# SNAC_hdmi-mini.net
KiCad netlist of a schematic drawn in EAGLE
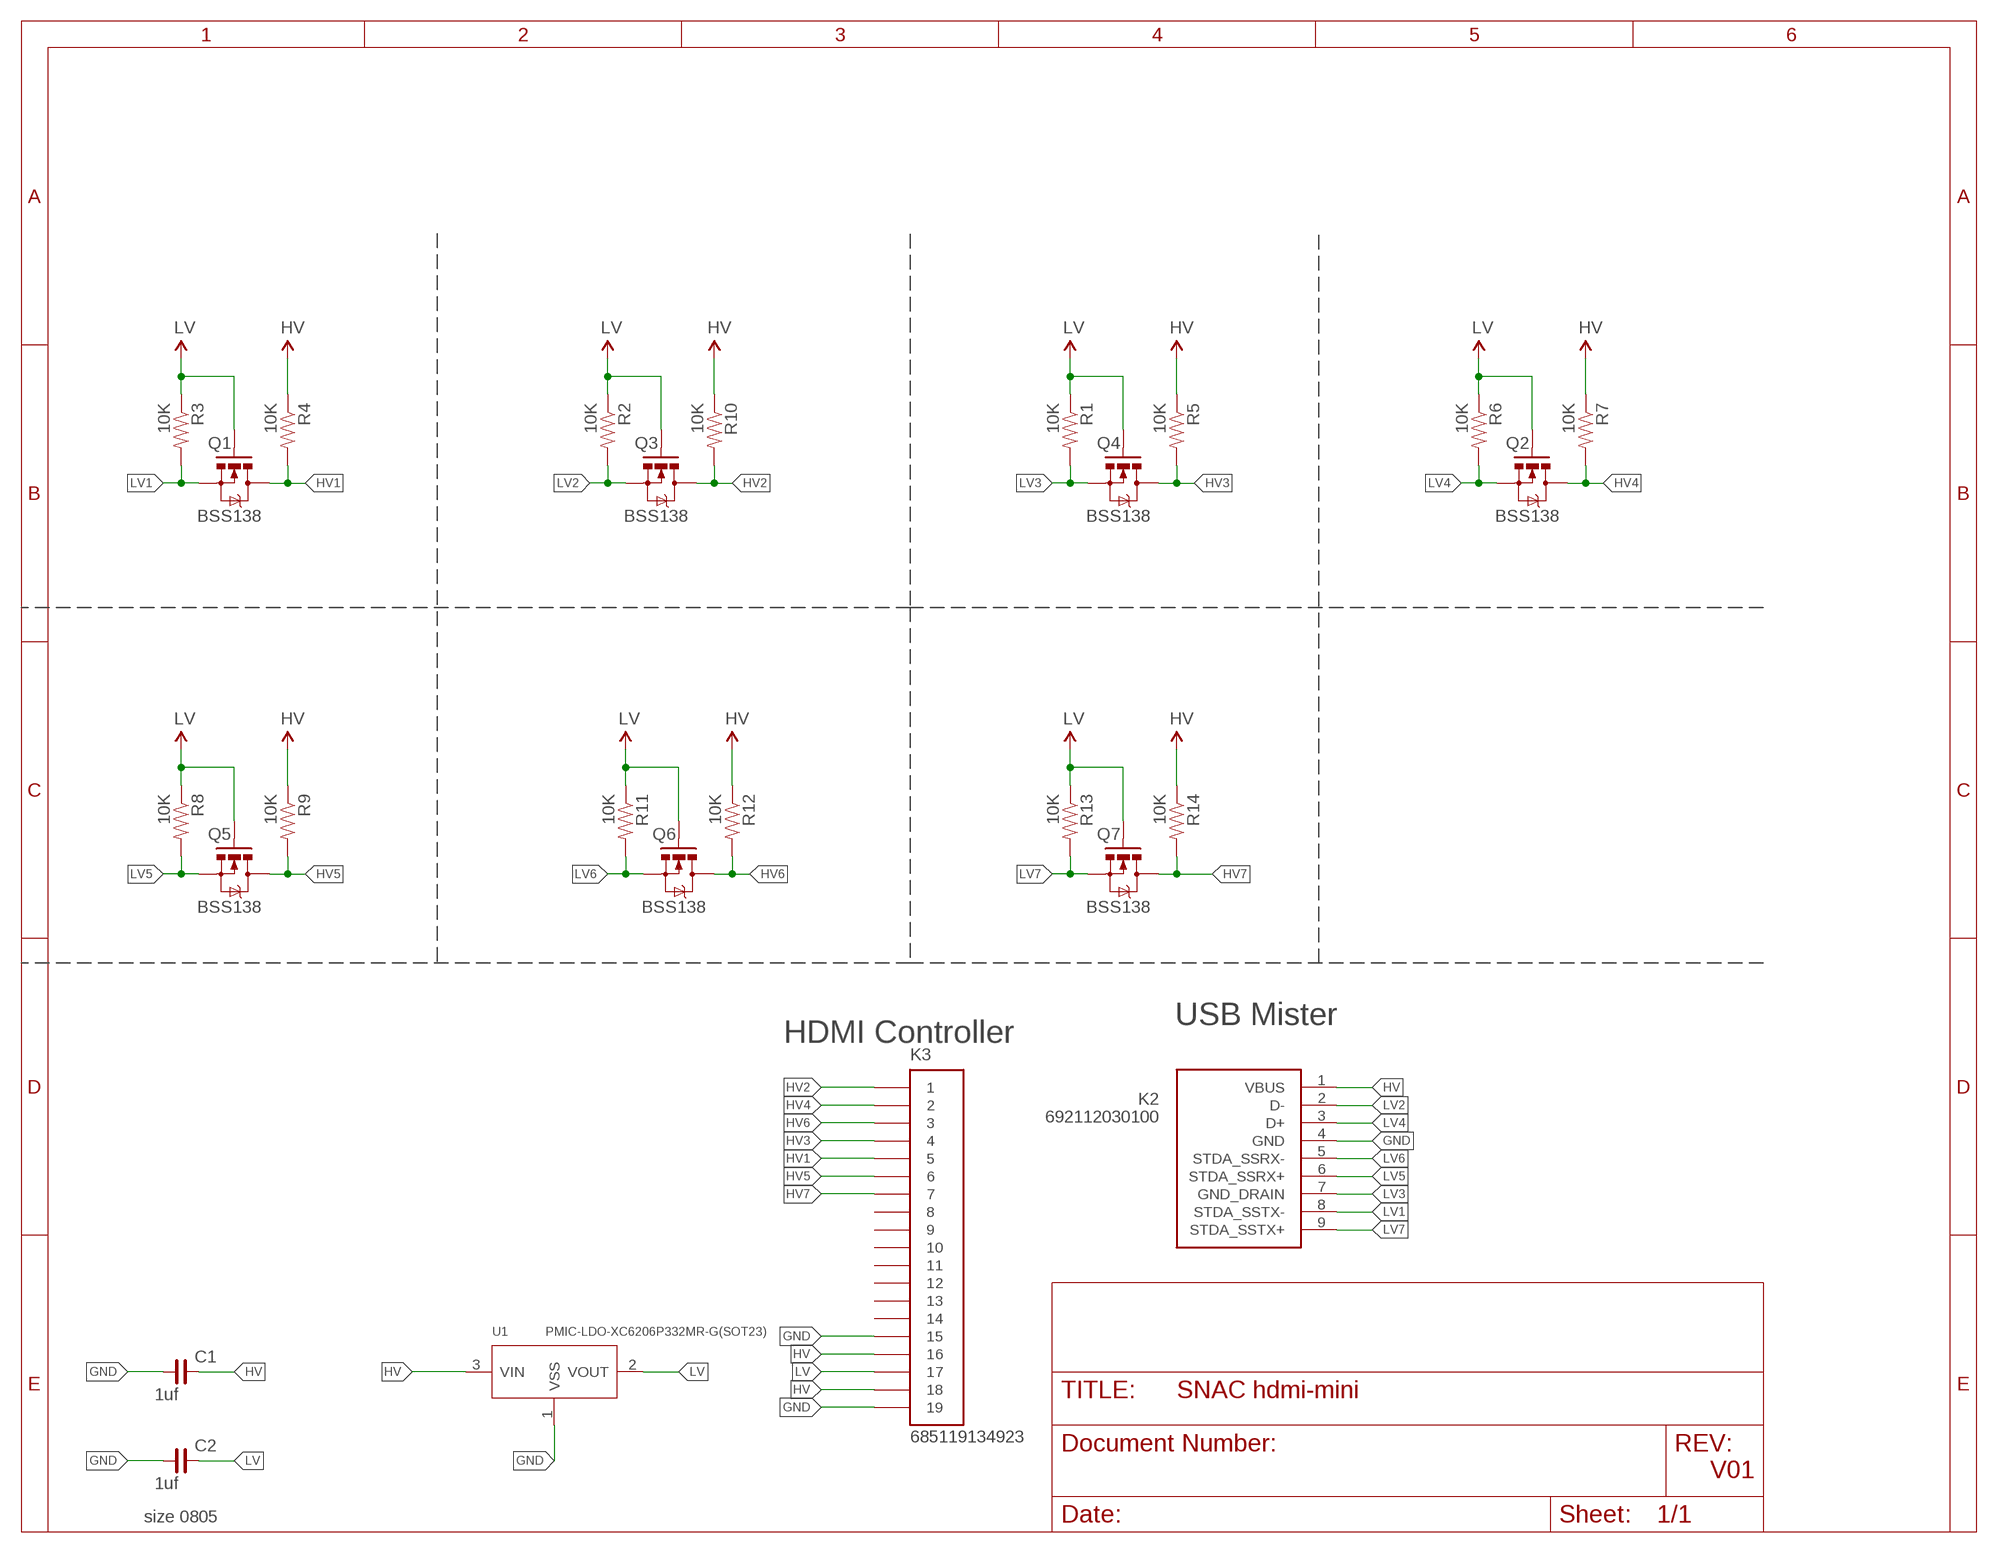
[diagram p0: schematic, sheet 1]

(export (version "E")
  (design (tool "Eeschema 10.0.6"))
  (components
    (comp (ref "C1")
      (value "1uf")
      (footprint "eagle-import:C0805")
      (libsource (lib "eagle-import") (part "C_0805"))
    )
    (comp (ref "C2")
      (value "1uf")
      (footprint "eagle-import:C0805")
      (libsource (lib "eagle-import") (part "C_0805"))
    )
    (comp (ref "K2")
      (value "692112030100")
      (footprint "eagle-import:692112030100")
      (libsource (lib "eagle-import") (part "692112030100"))
    )
    (comp (ref "K3")
      (value "685119134923")
      (footprint "eagle-import:685119134923")
      (libsource (lib "eagle-import") (part "685119134923"))
    )
    (comp (ref "Q1")
      (value "BSS138")
      (footprint "eagle-import:SOT23-3")
      (libsource (lib "eagle-import") (part "MOSFET-NCHANNELSMD"))
    )
    (comp (ref "Q2")
      (value "BSS138")
      (footprint "eagle-import:SOT23-3")
      (libsource (lib "eagle-import") (part "MOSFET-NCHANNELSMD"))
    )
    (comp (ref "Q3")
      (value "BSS138")
      (footprint "eagle-import:SOT23-3")
      (libsource (lib "eagle-import") (part "MOSFET-NCHANNELSMD"))
    )
    (comp (ref "Q4")
      (value "BSS138")
      (footprint "eagle-import:SOT23-3")
      (libsource (lib "eagle-import") (part "MOSFET-NCHANNELSMD"))
    )
    (comp (ref "Q5")
      (value "BSS138")
      (footprint "eagle-import:SOT23-3")
      (libsource (lib "eagle-import") (part "MOSFET-NCHANNELSMD"))
    )
    (comp (ref "Q6")
      (value "BSS138")
      (footprint "eagle-import:SOT23-3")
      (libsource (lib "eagle-import") (part "MOSFET-NCHANNELSMD"))
    )
    (comp (ref "Q7")
      (value "BSS138")
      (footprint "eagle-import:SOT23-3")
      (libsource (lib "eagle-import") (part "MOSFET-NCHANNELSMD"))
    )
    (comp (ref "R1")
      (value "10K")
      (footprint "eagle-import:0603-RES")
      (libsource (lib "eagle-import") (part "RESISTOR0603-RES"))
    )
    (comp (ref "R2")
      (value "10K")
      (footprint "eagle-import:0603-RES")
      (libsource (lib "eagle-import") (part "RESISTOR0603-RES"))
    )
    (comp (ref "R3")
      (value "10K")
      (footprint "eagle-import:0603-RES")
      (libsource (lib "eagle-import") (part "RESISTOR0603-RES"))
    )
    (comp (ref "R4")
      (value "10K")
      (footprint "eagle-import:0603-RES")
      (libsource (lib "eagle-import") (part "RESISTOR0603-RES"))
    )
    (comp (ref "R5")
      (value "10K")
      (footprint "eagle-import:0603-RES")
      (libsource (lib "eagle-import") (part "RESISTOR0603-RES"))
    )
    (comp (ref "R6")
      (value "10K")
      (footprint "eagle-import:0603-RES")
      (libsource (lib "eagle-import") (part "RESISTOR0603-RES"))
    )
    (comp (ref "R7")
      (value "10K")
      (footprint "eagle-import:0603-RES")
      (libsource (lib "eagle-import") (part "RESISTOR0603-RES"))
    )
    (comp (ref "R8")
      (value "10K")
      (footprint "eagle-import:0603-RES")
      (libsource (lib "eagle-import") (part "RESISTOR0603-RES"))
    )
    (comp (ref "R9")
      (value "10K")
      (footprint "eagle-import:0603-RES")
      (libsource (lib "eagle-import") (part "RESISTOR0603-RES"))
    )
    (comp (ref "R10")
      (value "10K")
      (footprint "eagle-import:0603-RES")
      (libsource (lib "eagle-import") (part "RESISTOR0603-RES"))
    )
    (comp (ref "R11")
      (value "10K")
      (footprint "eagle-import:0603-RES")
      (libsource (lib "eagle-import") (part "RESISTOR0603-RES"))
    )
    (comp (ref "R12")
      (value "10K")
      (footprint "eagle-import:0603-RES")
      (libsource (lib "eagle-import") (part "RESISTOR0603-RES"))
    )
    (comp (ref "R13")
      (value "10K")
      (footprint "eagle-import:0603-RES")
      (libsource (lib "eagle-import") (part "RESISTOR0603-RES"))
    )
    (comp (ref "R14")
      (value "10K")
      (footprint "eagle-import:0603-RES")
      (libsource (lib "eagle-import") (part "RESISTOR0603-RES"))
    )
    (comp (ref "U1")
      (value "PMIC-LDO-XC6206P332MR-G(SOT23)")
      (footprint "eagle-import:SOT-23")
      (fields (field (name "MF") "Torex") (field (name "MP") "XC6206P332MR-G"))
      (libsource (lib "eagle-import") (part "PMIC-LDO-XC6206P332MR-G(SOT23)"))
    )
  )
  (nets
    (net (code "1") (name "GND") (class "Default")
      (node (ref "C1") (pin "1") (pinfunction "1_1") (pintype "passive"))
      (node (ref "C2") (pin "1") (pinfunction "1_1") (pintype "passive"))
      (node (ref "K2") (pin "4") (pinfunction "GND_4") (pintype "bidirectional"))
      (node (ref "K3") (pin "15") (pinfunction "15_15") (pintype "passive"))
      (node (ref "K3") (pin "19") (pinfunction "19_19") (pintype "passive"))
      (node (ref "U1") (pin "1") (pinfunction "VSS_1") (pintype "power_in"))
    )
    (net (code "2") (name "HV") (class "Default")
      (node (ref "C1") (pin "2") (pinfunction "2_2") (pintype "passive"))
      (node (ref "K2") (pin "1") (pinfunction "VBUS_1") (pintype "bidirectional"))
      (node (ref "K3") (pin "16") (pinfunction "16_16") (pintype "passive"))
      (node (ref "K3") (pin "18") (pinfunction "18_18") (pintype "passive"))
      (node (ref "R10") (pin "1") (pinfunction "1_1") (pintype "passive"))
      (node (ref "R12") (pin "1") (pinfunction "1_1") (pintype "passive"))
      (node (ref "R14") (pin "1") (pinfunction "1_1") (pintype "passive"))
      (node (ref "R4") (pin "1") (pinfunction "1_1") (pintype "passive"))
      (node (ref "R5") (pin "1") (pinfunction "1_1") (pintype "passive"))
      (node (ref "R7") (pin "1") (pinfunction "1_1") (pintype "passive"))
      (node (ref "R9") (pin "1") (pinfunction "1_1") (pintype "passive"))
      (node (ref "U1") (pin "3") (pinfunction "VIN_3") (pintype "input"))
    )
    (net (code "3") (name "HV1") (class "Default")
      (node (ref "K3") (pin "5") (pinfunction "5_5") (pintype "passive"))
      (node (ref "Q1") (pin "3") (pinfunction "D_3") (pintype "passive"))
      (node (ref "R4") (pin "2") (pinfunction "2_2") (pintype "passive"))
    )
    (net (code "4") (name "HV2") (class "Default")
      (node (ref "K3") (pin "1") (pinfunction "1_1") (pintype "passive"))
      (node (ref "Q3") (pin "3") (pinfunction "D_3") (pintype "passive"))
      (node (ref "R10") (pin "2") (pinfunction "2_2") (pintype "passive"))
    )
    (net (code "5") (name "HV3") (class "Default")
      (node (ref "K3") (pin "4") (pinfunction "4_4") (pintype "passive"))
      (node (ref "Q4") (pin "3") (pinfunction "D_3") (pintype "passive"))
      (node (ref "R5") (pin "2") (pinfunction "2_2") (pintype "passive"))
    )
    (net (code "6") (name "HV4") (class "Default")
      (node (ref "K3") (pin "2") (pinfunction "2_2") (pintype "passive"))
      (node (ref "Q2") (pin "3") (pinfunction "D_3") (pintype "passive"))
      (node (ref "R7") (pin "2") (pinfunction "2_2") (pintype "passive"))
    )
    (net (code "7") (name "HV5") (class "Default")
      (node (ref "K3") (pin "6") (pinfunction "6_6") (pintype "passive"))
      (node (ref "Q5") (pin "3") (pinfunction "D_3") (pintype "passive"))
      (node (ref "R9") (pin "2") (pinfunction "2_2") (pintype "passive"))
    )
    (net (code "8") (name "HV6") (class "Default")
      (node (ref "K3") (pin "3") (pinfunction "3_3") (pintype "passive"))
      (node (ref "Q6") (pin "3") (pinfunction "D_3") (pintype "passive"))
      (node (ref "R12") (pin "2") (pinfunction "2_2") (pintype "passive"))
    )
    (net (code "9") (name "HV7") (class "Default")
      (node (ref "K3") (pin "7") (pinfunction "7_7") (pintype "passive"))
      (node (ref "Q7") (pin "3") (pinfunction "D_3") (pintype "passive"))
      (node (ref "R14") (pin "2") (pinfunction "2_2") (pintype "passive"))
    )
    (net (code "10") (name "LV") (class "Default")
      (node (ref "C2") (pin "2") (pinfunction "2_2") (pintype "passive"))
      (node (ref "K3") (pin "17") (pinfunction "17_17") (pintype "passive"))
      (node (ref "Q1") (pin "1") (pinfunction "G_1") (pintype "passive"))
      (node (ref "Q2") (pin "1") (pinfunction "G_1") (pintype "passive"))
      (node (ref "Q3") (pin "1") (pinfunction "G_1") (pintype "passive"))
      (node (ref "Q4") (pin "1") (pinfunction "G_1") (pintype "passive"))
      (node (ref "Q5") (pin "1") (pinfunction "G_1") (pintype "passive"))
      (node (ref "Q6") (pin "1") (pinfunction "G_1") (pintype "passive"))
      (node (ref "Q7") (pin "1") (pinfunction "G_1") (pintype "passive"))
      (node (ref "R1") (pin "1") (pinfunction "1_1") (pintype "passive"))
      (node (ref "R11") (pin "1") (pinfunction "1_1") (pintype "passive"))
      (node (ref "R13") (pin "1") (pinfunction "1_1") (pintype "passive"))
      (node (ref "R2") (pin "1") (pinfunction "1_1") (pintype "passive"))
      (node (ref "R3") (pin "1") (pinfunction "1_1") (pintype "passive"))
      (node (ref "R6") (pin "1") (pinfunction "1_1") (pintype "passive"))
      (node (ref "R8") (pin "1") (pinfunction "1_1") (pintype "passive"))
      (node (ref "U1") (pin "2") (pinfunction "VOUT_2") (pintype "output"))
    )
    (net (code "11") (name "LV1") (class "Default")
      (node (ref "K2") (pin "8") (pinfunction "STDA_SSTX-_8") (pintype "bidirectional"))
      (node (ref "Q1") (pin "2") (pinfunction "S_2") (pintype "passive"))
      (node (ref "R3") (pin "2") (pinfunction "2_2") (pintype "passive"))
    )
    (net (code "12") (name "LV2") (class "Default")
      (node (ref "K2") (pin "2") (pinfunction "D-_2") (pintype "bidirectional"))
      (node (ref "Q3") (pin "2") (pinfunction "S_2") (pintype "passive"))
      (node (ref "R2") (pin "2") (pinfunction "2_2") (pintype "passive"))
    )
    (net (code "13") (name "LV3") (class "Default")
      (node (ref "K2") (pin "7") (pinfunction "GND_DRAIN_7") (pintype "bidirectional"))
      (node (ref "Q4") (pin "2") (pinfunction "S_2") (pintype "passive"))
      (node (ref "R1") (pin "2") (pinfunction "2_2") (pintype "passive"))
    )
    (net (code "14") (name "LV4") (class "Default")
      (node (ref "K2") (pin "3") (pinfunction "D+_3") (pintype "bidirectional"))
      (node (ref "Q2") (pin "2") (pinfunction "S_2") (pintype "passive"))
      (node (ref "R6") (pin "2") (pinfunction "2_2") (pintype "passive"))
    )
    (net (code "15") (name "LV5") (class "Default")
      (node (ref "K2") (pin "6") (pinfunction "STDA_SSRX+_6") (pintype "bidirectional"))
      (node (ref "Q5") (pin "2") (pinfunction "S_2") (pintype "passive"))
      (node (ref "R8") (pin "2") (pinfunction "2_2") (pintype "passive"))
    )
    (net (code "16") (name "LV6") (class "Default")
      (node (ref "K2") (pin "5") (pinfunction "STDA_SSRX-_5") (pintype "bidirectional"))
      (node (ref "Q6") (pin "2") (pinfunction "S_2") (pintype "passive"))
      (node (ref "R11") (pin "2") (pinfunction "2_2") (pintype "passive"))
    )
    (net (code "17") (name "LV7") (class "Default")
      (node (ref "K2") (pin "9") (pinfunction "STDA_SSTX+_9") (pintype "bidirectional"))
      (node (ref "Q7") (pin "2") (pinfunction "S_2") (pintype "passive"))
      (node (ref "R13") (pin "2") (pinfunction "2_2") (pintype "passive"))
    )
    (net (code "18") (name "unconnected-(K3-Pad8)") (class "Default")
      (node (ref "K3") (pin "8") (pinfunction "8_8") (pintype "passive"))
    )
    (net (code "19") (name "unconnected-(K3-Pad9)") (class "Default")
      (node (ref "K3") (pin "9") (pinfunction "9_9") (pintype "passive"))
    )
    (net (code "20") (name "unconnected-(K3-Pad10)") (class "Default")
      (node (ref "K3") (pin "10") (pinfunction "10_10") (pintype "passive"))
    )
    (net (code "21") (name "unconnected-(K3-Pad11)") (class "Default")
      (node (ref "K3") (pin "11") (pinfunction "11_11") (pintype "passive"))
    )
    (net (code "22") (name "unconnected-(K3-Pad12)") (class "Default")
      (node (ref "K3") (pin "12") (pinfunction "12_12") (pintype "passive"))
    )
    (net (code "23") (name "unconnected-(K3-Pad13)") (class "Default")
      (node (ref "K3") (pin "13") (pinfunction "13_13") (pintype "passive"))
    )
    (net (code "24") (name "unconnected-(K3-Pad14)") (class "Default")
      (node (ref "K3") (pin "14") (pinfunction "14_14") (pintype "passive"))
    )
  )
)
